# tes1.net
KiCad netlist of a schematic drawn in EAGLE
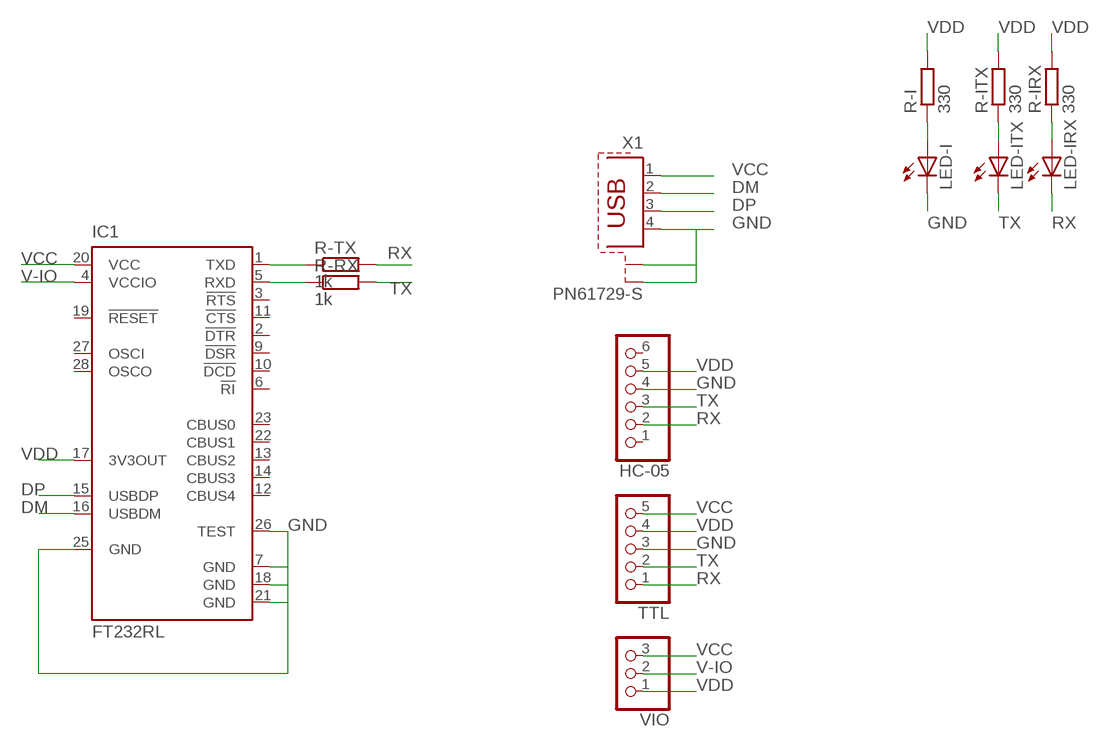
[diagram p0: schematic, sheet 1]

(export (version "E")
  (design (tool "Eeschema 10.0.6"))
  (components
    (comp (ref "HC-05")
      (value "PINHD-1X6")
      (footprint "eagle-import:1X06")
      (libsource (lib "eagle-import") (part "PINHD-1X6"))
    )
    (comp (ref "IC1")
      (value "FT232RL")
      (footprint "eagle-import:SSOP28")
      (libsource (lib "eagle-import") (part "FT232RL"))
    )
    (comp (ref "LED-I")
      (value "LED3MM")
      (footprint "eagle-import:LED3MM")
      (libsource (lib "eagle-import") (part "LED3MM"))
    )
    (comp (ref "LED-IRX")
      (value "LED3MM")
      (footprint "eagle-import:LED3MM")
      (libsource (lib "eagle-import") (part "LED3MM"))
    )
    (comp (ref "LED-ITX")
      (value "LED3MM")
      (footprint "eagle-import:LED3MM")
      (libsource (lib "eagle-import") (part "LED3MM"))
    )
    (comp (ref "R-I")
      (value "330")
      (footprint "eagle-import:0204_7")
      (libsource (lib "eagle-import") (part "R-EU_0204/7"))
    )
    (comp (ref "R-IRX")
      (value "330")
      (footprint "eagle-import:0204_7")
      (libsource (lib "eagle-import") (part "R-EU_0204/7"))
    )
    (comp (ref "R-ITX")
      (value "330")
      (footprint "eagle-import:0204_7")
      (libsource (lib "eagle-import") (part "R-EU_0204/7"))
    )
    (comp (ref "R-RX")
      (value "1k")
      (footprint "eagle-import:0204_7")
      (libsource (lib "eagle-import") (part "R-EU_0204/7"))
    )
    (comp (ref "R-TX")
      (value "1k")
      (footprint "eagle-import:0204_7")
      (libsource (lib "eagle-import") (part "R-EU_0204/7"))
    )
    (comp (ref "TTL")
      (value "PINHD-1X5")
      (footprint "eagle-import:1X05")
      (libsource (lib "eagle-import") (part "PINHD-1X5"))
    )
    (comp (ref "VIO")
      (value "PINHD-1X3")
      (footprint "eagle-import:1X03")
      (libsource (lib "eagle-import") (part "PINHD-1X3"))
    )
    (comp (ref "X1")
      (value "PN61729-S")
      (footprint "eagle-import:PN61729-S")
      (libsource (lib "eagle-import") (part "PN61729-S"))
    )
  )
  (nets
    (net (code "1") (name "/DM") (class "Default")
      (node (ref "IC1") (pin "16") (pinfunction "USBDM_16") (pintype "bidirectional"))
      (node (ref "X1") (pin "2") (pinfunction "2_2") (pintype "passive"))
    )
    (net (code "2") (name "/DP") (class "Default")
      (node (ref "IC1") (pin "15") (pinfunction "USBDP_15") (pintype "bidirectional"))
      (node (ref "X1") (pin "3") (pinfunction "3_3") (pintype "passive"))
    )
    (net (code "3") (name "/GND") (class "Default")
      (node (ref "HC-05") (pin "4") (pinfunction "4_4") (pintype "passive"))
      (node (ref "IC1") (pin "18") (pinfunction "GND_18") (pintype "power_in"))
      (node (ref "IC1") (pin "21") (pinfunction "GND_21") (pintype "power_in"))
      (node (ref "IC1") (pin "25") (pinfunction "GND_25") (pintype "power_in"))
      (node (ref "IC1") (pin "26") (pinfunction "TEST_26") (pintype "input"))
      (node (ref "IC1") (pin "7") (pinfunction "GND_7") (pintype "power_in"))
      (node (ref "LED-I") (pin "K") (pinfunction "C_K") (pintype "passive"))
      (node (ref "TTL") (pin "3") (pinfunction "3_3") (pintype "passive"))
      (node (ref "X1") (pin "4") (pinfunction "4_4") (pintype "passive"))
      (node (ref "X1") (pin "S1") (pinfunction "S1_S1") (pintype "passive"))
      (node (ref "X1") (pin "S2") (pinfunction "S2_S2") (pintype "passive"))
    )
    (net (code "4") (name "/RX") (class "Default")
      (node (ref "HC-05") (pin "2") (pinfunction "2_2") (pintype "passive"))
      (node (ref "LED-IRX") (pin "K") (pinfunction "C_K") (pintype "passive"))
      (node (ref "R-TX") (pin "2") (pinfunction "2_2") (pintype "passive"))
      (node (ref "TTL") (pin "1") (pinfunction "1_1") (pintype "passive"))
    )
    (net (code "5") (name "/TX") (class "Default")
      (node (ref "HC-05") (pin "3") (pinfunction "3_3") (pintype "passive"))
      (node (ref "LED-ITX") (pin "K") (pinfunction "C_K") (pintype "passive"))
      (node (ref "R-RX") (pin "2") (pinfunction "2_2") (pintype "passive"))
      (node (ref "TTL") (pin "2") (pinfunction "2_2") (pintype "passive"))
    )
    (net (code "6") (name "/V-IO") (class "Default")
      (node (ref "IC1") (pin "4") (pinfunction "VCCIO_4") (pintype "power_in"))
      (node (ref "VIO") (pin "2") (pinfunction "2_2") (pintype "passive"))
    )
    (net (code "7") (name "/VCC") (class "Default")
      (node (ref "IC1") (pin "20") (pinfunction "VCC_20") (pintype "power_in"))
      (node (ref "TTL") (pin "5") (pinfunction "5_5") (pintype "passive"))
      (node (ref "VIO") (pin "3") (pinfunction "3_3") (pintype "passive"))
      (node (ref "X1") (pin "1") (pinfunction "1_1") (pintype "passive"))
    )
    (net (code "8") (name "/VDD") (class "Default")
      (node (ref "HC-05") (pin "5") (pinfunction "5_5") (pintype "passive"))
      (node (ref "IC1") (pin "17") (pinfunction "3V3OUT_17") (pintype "output"))
      (node (ref "R-I") (pin "2") (pinfunction "2_2") (pintype "passive"))
      (node (ref "R-IRX") (pin "2") (pinfunction "2_2") (pintype "passive"))
      (node (ref "R-ITX") (pin "2") (pinfunction "2_2") (pintype "passive"))
      (node (ref "TTL") (pin "4") (pinfunction "4_4") (pintype "passive"))
      (node (ref "VIO") (pin "1") (pinfunction "1_1") (pintype "passive"))
    )
    (net (code "9") (name "Net-(IC1-RXD)") (class "Default")
      (node (ref "IC1") (pin "5") (pinfunction "RXD_5") (pintype "input"))
      (node (ref "R-RX") (pin "1") (pinfunction "1_1") (pintype "passive"))
    )
    (net (code "10") (name "Net-(IC1-TXD)") (class "Default")
      (node (ref "IC1") (pin "1") (pinfunction "TXD_1") (pintype "output"))
      (node (ref "R-TX") (pin "1") (pinfunction "1_1") (pintype "passive"))
    )
    (net (code "11") (name "Net-(LED-I-PadA)") (class "Default")
      (node (ref "LED-I") (pin "A") (pinfunction "A_A") (pintype "passive"))
      (node (ref "R-I") (pin "1") (pinfunction "1_1") (pintype "passive"))
    )
    (net (code "12") (name "Net-(LED-IRX-PadA)") (class "Default")
      (node (ref "LED-IRX") (pin "A") (pinfunction "A_A") (pintype "passive"))
      (node (ref "R-IRX") (pin "1") (pinfunction "1_1") (pintype "passive"))
    )
    (net (code "13") (name "Net-(LED-ITX-PadA)") (class "Default")
      (node (ref "LED-ITX") (pin "A") (pinfunction "A_A") (pintype "passive"))
      (node (ref "R-ITX") (pin "1") (pinfunction "1_1") (pintype "passive"))
    )
    (net (code "14") (name "unconnected-(HC-05-Pad1)") (class "Default")
      (node (ref "HC-05") (pin "1") (pinfunction "1_1") (pintype "passive"))
    )
    (net (code "15") (name "unconnected-(HC-05-Pad6)") (class "Default")
      (node (ref "HC-05") (pin "6") (pinfunction "6_6") (pintype "passive"))
    )
    (net (code "16") (name "unconnected-(IC1-CBUS0-Pad23)") (class "Default")
      (node (ref "IC1") (pin "23") (pinfunction "CBUS0_23") (pintype "bidirectional"))
    )
    (net (code "17") (name "unconnected-(IC1-CBUS1-Pad22)") (class "Default")
      (node (ref "IC1") (pin "22") (pinfunction "CBUS1_22") (pintype "bidirectional"))
    )
    (net (code "18") (name "unconnected-(IC1-CBUS2-Pad13)") (class "Default")
      (node (ref "IC1") (pin "13") (pinfunction "CBUS2_13") (pintype "bidirectional"))
    )
    (net (code "19") (name "unconnected-(IC1-CBUS3-Pad14)") (class "Default")
      (node (ref "IC1") (pin "14") (pinfunction "CBUS3_14") (pintype "bidirectional"))
    )
    (net (code "20") (name "unconnected-(IC1-CBUS4-Pad12)") (class "Default")
      (node (ref "IC1") (pin "12") (pinfunction "CBUS4_12") (pintype "bidirectional"))
    )
    (net (code "21") (name "unconnected-(IC1-OSCI-Pad27)") (class "Default")
      (node (ref "IC1") (pin "27") (pinfunction "OSCI_27") (pintype "input"))
    )
    (net (code "22") (name "unconnected-(IC1-OSCO-Pad28)") (class "Default")
      (node (ref "IC1") (pin "28") (pinfunction "OSCO_28") (pintype "output"))
    )
    (net (code "23") (name "unconnected-(IC1-~{CTS}-Pad11)") (class "Default")
      (node (ref "IC1") (pin "11") (pinfunction "~{CTS}_11") (pintype "input"))
    )
    (net (code "24") (name "unconnected-(IC1-~{DCD}-Pad10)") (class "Default")
      (node (ref "IC1") (pin "10") (pinfunction "~{DCD}_10") (pintype "input"))
    )
    (net (code "25") (name "unconnected-(IC1-~{DSR}-Pad9)") (class "Default")
      (node (ref "IC1") (pin "9") (pinfunction "~{DSR}_9") (pintype "input"))
    )
    (net (code "26") (name "unconnected-(IC1-~{DTR}-Pad2)") (class "Default")
      (node (ref "IC1") (pin "2") (pinfunction "~{DTR}_2") (pintype "output"))
    )
    (net (code "27") (name "unconnected-(IC1-~{RESET}-Pad19)") (class "Default")
      (node (ref "IC1") (pin "19") (pinfunction "~{RESET}_19") (pintype "input"))
    )
    (net (code "28") (name "unconnected-(IC1-~{RI}-Pad6)") (class "Default")
      (node (ref "IC1") (pin "6") (pinfunction "~{RI}_6") (pintype "input"))
    )
    (net (code "29") (name "unconnected-(IC1-~{RTS}-Pad3)") (class "Default")
      (node (ref "IC1") (pin "3") (pinfunction "~{RTS}_3") (pintype "output"))
    )
  )
)
